# 04-SNESDRONE_Direct_IO_LEVEL_SHIFTER_1.net
KiCad netlist of a schematic drawn in Altium Designer
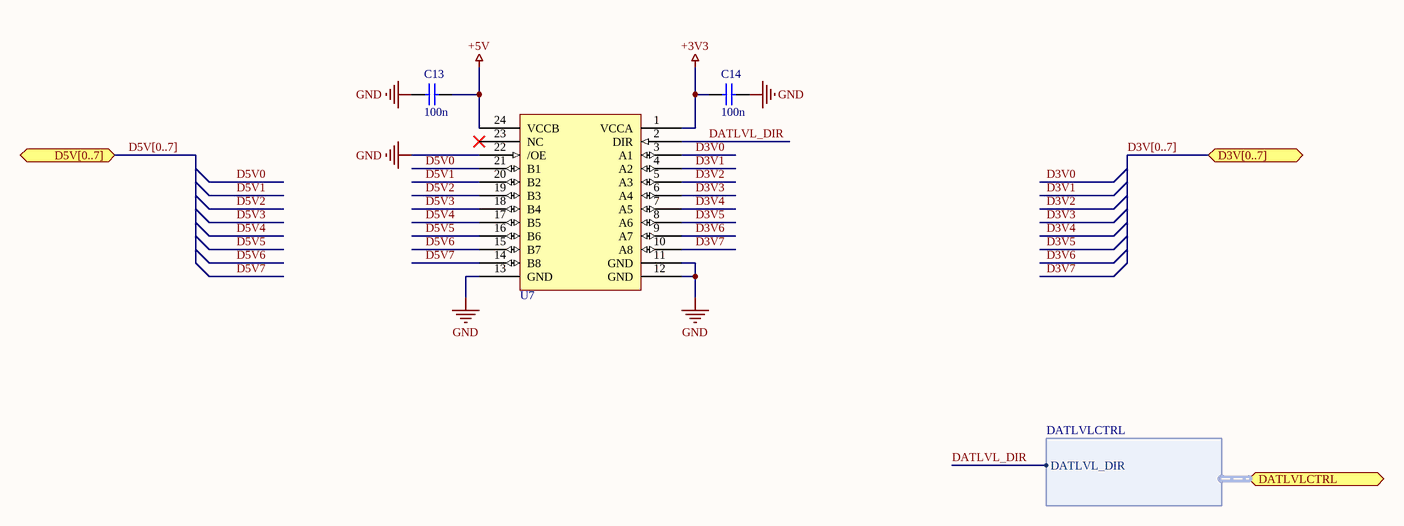
[diagram p0: 04-SNESDRONE_Direct_IO_LEVEL_SHIFTER_1.SchDoc]

(export (version "E")
  (design (tool "Eeschema 10.0.6"))
  (components
    (comp (ref "C13")
      (value "100n")
      (footprint "cap_0603")
      (description "Capacitor")
      (fields (field (name "Comment") "cap_0603"))
      (libsource (lib "mycomponents") (part "cap_0603"))
    )
    (comp (ref "C14")
      (value "100n")
      (footprint "cap_0603")
      (description "Capacitor")
      (fields (field (name "Comment") "cap_0603"))
      (libsource (lib "mycomponents") (part "cap_0603"))
    )
    (comp (ref "U7")
      (value "IC_SN74LVCC3245APWR")
      (footprint "TSSOP24")
      (description "Bus-Transceiver, Produktreihe LVC, 8 Eingänge, 50mA, 7ns, 2.3V bis 5.5V, TSSOP 24")
      (libsource (lib "mycomponents") (part "IC_SN74LVCC3245APWR"))
    )
  )
  (nets
    (net (code "2") (name "+3V3") (class "Default")
      (node (ref "C14") (pin "2") (pinfunction "2_2") (pintype "passive"))
      (node (ref "U7") (pin "1") (pinfunction "VCCA_1") (pintype "power_in"))
    )
    (net (code "3") (name "+5V") (class "Default")
      (node (ref "C13") (pin "1") (pinfunction "1_1") (pintype "passive"))
      (node (ref "U7") (pin "24") (pinfunction "VCCB_24") (pintype "power_in"))
    )
    (net (code "4") (name "/D3V0") (class "Default")
      (node (ref "U7") (pin "3") (pinfunction "A1_3") (pintype "bidirectional"))
    )
    (net (code "5") (name "/D3V1") (class "Default")
      (node (ref "U7") (pin "4") (pinfunction "A2_4") (pintype "bidirectional"))
    )
    (net (code "6") (name "/D3V2") (class "Default")
      (node (ref "U7") (pin "5") (pinfunction "A3_5") (pintype "bidirectional"))
    )
    (net (code "7") (name "/D3V3") (class "Default")
      (node (ref "U7") (pin "6") (pinfunction "A4_6") (pintype "bidirectional"))
    )
    (net (code "8") (name "/D3V4") (class "Default")
      (node (ref "U7") (pin "7") (pinfunction "A5_7") (pintype "bidirectional"))
    )
    (net (code "9") (name "/D3V5") (class "Default")
      (node (ref "U7") (pin "8") (pinfunction "A6_8") (pintype "bidirectional"))
    )
    (net (code "10") (name "/D3V6") (class "Default")
      (node (ref "U7") (pin "9") (pinfunction "A7_9") (pintype "bidirectional"))
    )
    (net (code "11") (name "/D3V7") (class "Default")
      (node (ref "U7") (pin "10") (pinfunction "A8_10") (pintype "bidirectional"))
    )
    (net (code "13") (name "/D5V0") (class "Default")
      (node (ref "U7") (pin "21") (pinfunction "B1_21") (pintype "bidirectional"))
    )
    (net (code "14") (name "/D5V1") (class "Default")
      (node (ref "U7") (pin "20") (pinfunction "B2_20") (pintype "bidirectional"))
    )
    (net (code "15") (name "/D5V2") (class "Default")
      (node (ref "U7") (pin "19") (pinfunction "B3_19") (pintype "bidirectional"))
    )
    (net (code "16") (name "/D5V3") (class "Default")
      (node (ref "U7") (pin "18") (pinfunction "B4_18") (pintype "bidirectional"))
    )
    (net (code "17") (name "/D5V4") (class "Default")
      (node (ref "U7") (pin "17") (pinfunction "B5_17") (pintype "bidirectional"))
    )
    (net (code "18") (name "/D5V5") (class "Default")
      (node (ref "U7") (pin "16") (pinfunction "B6_16") (pintype "bidirectional"))
    )
    (net (code "19") (name "/D5V6") (class "Default")
      (node (ref "U7") (pin "15") (pinfunction "B7_15") (pintype "bidirectional"))
    )
    (net (code "20") (name "/D5V7") (class "Default")
      (node (ref "U7") (pin "14") (pinfunction "B8_14") (pintype "bidirectional"))
    )
    (net (code "22") (name "/DATLVL_DIR") (class "Default")
      (node (ref "U7") (pin "2") (pinfunction "DIR_2") (pintype "input"))
    )
    (net (code "24") (name "GND") (class "Default")
      (node (ref "C13") (pin "2") (pinfunction "2_2") (pintype "passive"))
      (node (ref "C14") (pin "1") (pinfunction "1_1") (pintype "passive"))
      (node (ref "U7") (pin "11") (pinfunction "GND_11") (pintype "power_in"))
      (node (ref "U7") (pin "12") (pinfunction "GND_12") (pintype "power_in"))
      (node (ref "U7") (pin "13") (pinfunction "GND_13") (pintype "power_in"))
      (node (ref "U7") (pin "22") (pinfunction "/OE_22") (pintype "input"))
    )
    (net (code "25") (name "unconnected-(U7-NC-Pad23)") (class "Default")
      (node (ref "U7") (pin "23") (pinfunction "NC_23") (pintype "passive+no_connect"))
    )
  )
)
